# booz_power_board.net
KiCad netlist of a schematic drawn in Altium Designer
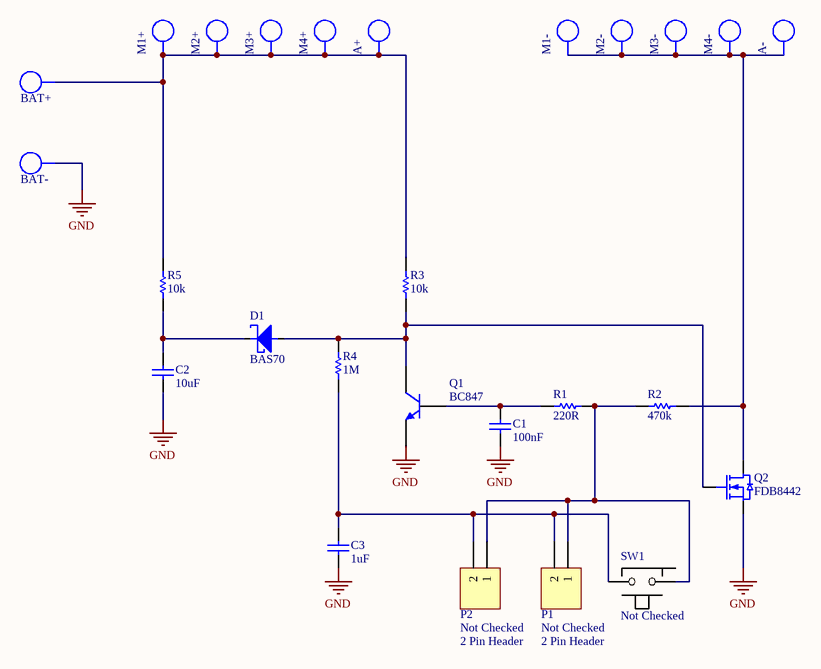
[diagram p0: booz_power_board.SchDoc]

(export (version "E")
  (design (tool "Eeschema 10.0.6"))
  (components
    (comp (ref "A+")
      (value "~")
      (footprint "BOOZ_MOTOR")
      (description "Pad for booz power board")
      (libsource (lib "GRC sch library") (part "JP_BOOZ_PAD"))
    )
    (comp (ref "A-")
      (value "~")
      (footprint "BOOZ_MOTOR")
      (description "Pad for booz power board")
      (libsource (lib "GRC sch library") (part "JP_BOOZ_PAD"))
    )
    (comp (ref "BAT+")
      (value "~")
      (footprint "BOOZ_POWER")
      (description "Pad for booz power board")
      (libsource (lib "GRC sch library") (part "JP_BOOZ_PAD"))
    )
    (comp (ref "BAT-")
      (value "~")
      (footprint "BOOZ_POWER")
      (description "Pad for booz power board")
      (libsource (lib "GRC sch library") (part "JP_BOOZ_PAD"))
    )
    (comp (ref "C1")
      (value "100nF")
      (footprint "GRC PCB library:0603")
      (description "CAP CER .10UF 50V X5R 0603")
      (fields (field (name "MANUFACTURER") "Taiyo Yuden"))
      (libsource (lib "GRC sch library") (part "CP_100nF 0603"))
    )
    (comp (ref "C2")
      (value "10uF")
      (footprint "GRC PCB library:1206")
      (description "CAP CER 10uF 25V X5R 1206")
      (fields (field (name "MANUFACTURER") "Panasonic") (field (name "Comment") "CP_10uF_25V_1206"))
      (libsource (lib "GRC sch library") (part "CP_10uF_25V_1206"))
    )
    (comp (ref "C3")
      (value "1uF")
      (footprint "GRC PCB library:0603")
      (description "CAP CER 1.0UF 50V X5S 0603")
      (fields (field (name "MANUFACTURER") "Taiyo Yuden"))
      (libsource (lib "GRC sch library") (part "CP_1uF 0603"))
    )
    (comp (ref "D1")
      (value "BAS70")
      (footprint "SOT23")
      (description "DIODE SCHOTTKY 70V 200MA SOT23")
      (fields (field (name "MANUFACTURER") "ST Micro"))
      (libsource (lib "GRC sch library") (part "DS_BAS70"))
    )
    (comp (ref "M1+")
      (value "~")
      (footprint "BOOZ_MOTOR")
      (description "Pad for booz power board")
      (libsource (lib "GRC sch library") (part "JP_BOOZ_PAD"))
    )
    (comp (ref "M1-")
      (value "~")
      (footprint "BOOZ_MOTOR")
      (description "Pad for booz power board")
      (libsource (lib "GRC sch library") (part "JP_BOOZ_PAD"))
    )
    (comp (ref "M2+")
      (value "~")
      (footprint "BOOZ_MOTOR")
      (description "Pad for booz power board")
      (libsource (lib "GRC sch library") (part "JP_BOOZ_PAD"))
    )
    (comp (ref "M2-")
      (value "~")
      (footprint "BOOZ_MOTOR")
      (description "Pad for booz power board")
      (libsource (lib "GRC sch library") (part "JP_BOOZ_PAD"))
    )
    (comp (ref "M3+")
      (value "~")
      (footprint "BOOZ_MOTOR")
      (description "Pad for booz power board")
      (libsource (lib "GRC sch library") (part "JP_BOOZ_PAD"))
    )
    (comp (ref "M3-")
      (value "~")
      (footprint "BOOZ_MOTOR")
      (description "Pad for booz power board")
      (libsource (lib "GRC sch library") (part "JP_BOOZ_PAD"))
    )
    (comp (ref "M4+")
      (value "~")
      (footprint "BOOZ_MOTOR")
      (description "Pad for booz power board")
      (libsource (lib "GRC sch library") (part "JP_BOOZ_PAD"))
    )
    (comp (ref "M4-")
      (value "~")
      (footprint "BOOZ_MOTOR")
      (description "Pad for booz power board")
      (libsource (lib "GRC sch library") (part "JP_BOOZ_PAD"))
    )
    (comp (ref "P1")
      (value "2 Pin Header")
      (footprint "CONN_2X1_SMT_RA_1.25MM")
      (description "CONN HDR VERT 2POS .100\" SNGL")
      (fields (field (name "MANUFACTURER") "Molex") (field (name "VERIFY") "Not Checked"))
      (libsource (lib "GRC sch library") (part "JP_2PIN HDR_SMT_RA_MOLEX"))
    )
    (comp (ref "P2")
      (value "2 Pin Header")
      (footprint "CONN_2X1_SMT_RA_1.25MM")
      (description "CONN HDR VERT 2POS .100\" SNGL")
      (fields (field (name "MANUFACTURER") "Molex") (field (name "VERIFY") "Not Checked"))
      (libsource (lib "GRC sch library") (part "JP_2PIN HDR_SMT_RA_MOLEX"))
    )
    (comp (ref "Q1")
      (value "BC847")
      (footprint "GRC PCB library:SOT23")
      (description "TRANS NPN GP 100MA 45V SOT23")
      (fields (field (name "MANUFACTURER") "NXP Semiconductors"))
      (libsource (lib "GRC sch library") (part "TN_BC847"))
    )
    (comp (ref "Q2")
      (value "FDB8442")
      (footprint "TO-263AB")
      (description "MOSFET N-CH 40V 80A D2PAK")
      (fields (field (name "MANUFACTURER") "Fairchild"))
      (libsource (lib "GRC sch library") (part "TF_FDB8442"))
    )
    (comp (ref "R1")
      (value "220R")
      (footprint "1206")
      (description "RES 220 OHM 1/4W 1% 1206 SMD")
      (fields (field (name "MANUFACTURER") "Vishay/Dale"))
      (libsource (lib "GRC sch library") (part "RS_220R 1206"))
    )
    (comp (ref "R2")
      (value "470k")
      (footprint "GRC PCB library:0603")
      (description "RES 470K OHM 1/10W 5% 0603 SMD")
      (fields (field (name "MANUFACTURER") "Yagep"))
      (libsource (lib "GRC sch library") (part "RS_470k 0603"))
    )
    (comp (ref "R3")
      (value "10k")
      (footprint "1206")
      (description "RES 10.0K OHM 1/4W 1% 1206 SMD")
      (fields (field (name "MANUFACTURER") "Vishay/Dale"))
      (libsource (lib "GRC sch library") (part "RS_10k 1206"))
    )
    (comp (ref "R4")
      (value "1M")
      (footprint "GRC PCB library:0603")
      (description "RES 1.00M OHM 1/10W 1% 0603 SMD")
      (fields (field (name "MANUFACTURER") "Yageo"))
      (libsource (lib "GRC sch library") (part "RS_1M 0603"))
    )
    (comp (ref "R5")
      (value "10k")
      (footprint "GRC PCB library:0603")
      (description "RES 10.0K OHM 1/10W 1% 0603 SMD")
      (fields (field (name "MANUFACTURER") "Yageo"))
      (libsource (lib "GRC sch library") (part "RS_10k 0603"))
    )
    (comp (ref "SW1")
      (value "Push Button Switch")
      (footprint "PUSHBUTTON_B3U")
      (description "SWITCH TACT RT ANG SPST SMD")
      (fields (field (name "MANUFACTURER") "Omron") (field (name "VERIFY") "Not Checked"))
      (libsource (lib "GRC sch library") (part "SW_TACT 3MM RT"))
    )
  )
  (nets
    (net (code "1") (name "GND") (class "Default")
      (node (ref "BAT-") (pin "1") (pinfunction "1_1") (pintype "power_in"))
      (node (ref "C1") (pin "1") (pinfunction "1_1") (pintype "passive"))
      (node (ref "C2") (pin "1") (pinfunction "1_1") (pintype "passive"))
      (node (ref "C3") (pin "1") (pinfunction "1_1") (pintype "passive"))
      (node (ref "Q1") (pin "2") (pinfunction "E_2") (pintype "passive"))
      (node (ref "Q2") (pin "3") (pinfunction "S_3") (pintype "passive"))
    )
    (net (code "2") (name "Net-(A+-Pad1)") (class "Default")
      (node (ref "A+") (pin "1") (pinfunction "1_1") (pintype "power_in"))
      (node (ref "BAT+") (pin "1") (pinfunction "1_1") (pintype "power_in"))
      (node (ref "M1+") (pin "1") (pinfunction "1_1") (pintype "power_in"))
      (node (ref "M2+") (pin "1") (pinfunction "1_1") (pintype "power_in"))
      (node (ref "M3+") (pin "1") (pinfunction "1_1") (pintype "power_in"))
      (node (ref "M4+") (pin "1") (pinfunction "1_1") (pintype "power_in"))
      (node (ref "R3") (pin "2") (pinfunction "2_2") (pintype "passive"))
      (node (ref "R5") (pin "2") (pinfunction "2_2") (pintype "passive"))
    )
    (net (code "3") (name "Net-(C3-Pad2)") (class "Default")
      (node (ref "C3") (pin "2") (pinfunction "2_2") (pintype "passive"))
      (node (ref "P1") (pin "2") (pinfunction "2_2") (pintype "passive"))
      (node (ref "P2") (pin "2") (pinfunction "2_2") (pintype "passive"))
      (node (ref "R4") (pin "1") (pinfunction "1_1") (pintype "passive"))
      (node (ref "SW1") (pin "2") (pinfunction "2_2") (pintype "passive"))
    )
    (net (code "4") (name "Net-(D1-A)") (class "Default")
      (node (ref "D1") (pin "1") (pinfunction "A_1") (pintype "passive"))
      (node (ref "Q1") (pin "3") (pinfunction "C_3") (pintype "passive"))
      (node (ref "Q2") (pin "1") (pinfunction "G_1") (pintype "passive"))
      (node (ref "R3") (pin "1") (pinfunction "1_1") (pintype "passive"))
      (node (ref "R4") (pin "2") (pinfunction "2_2") (pintype "passive"))
    )
    (net (code "5") (name "Net-(D1-K)") (class "Default")
      (node (ref "C2") (pin "2") (pinfunction "2_2") (pintype "passive"))
      (node (ref "D1") (pin "3") (pinfunction "K_3") (pintype "passive"))
      (node (ref "R5") (pin "1") (pinfunction "1_1") (pintype "passive"))
    )
    (net (code "6") (name "Net-(P1-Pad1)") (class "Default")
      (node (ref "P1") (pin "1") (pinfunction "1_1") (pintype "passive"))
      (node (ref "P2") (pin "1") (pinfunction "1_1") (pintype "passive"))
      (node (ref "R1") (pin "2") (pinfunction "2_2") (pintype "passive"))
      (node (ref "R2") (pin "1") (pinfunction "1_1") (pintype "passive"))
      (node (ref "SW1") (pin "1") (pinfunction "1_1") (pintype "passive"))
    )
    (net (code "7") (name "Net-(Q1-B)") (class "Default")
      (node (ref "C1") (pin "2") (pinfunction "2_2") (pintype "passive"))
      (node (ref "Q1") (pin "1") (pinfunction "B_1") (pintype "passive"))
      (node (ref "R1") (pin "1") (pinfunction "1_1") (pintype "passive"))
    )
    (net (code "8") (name "Net-(Q2-D)") (class "Default")
      (node (ref "A-") (pin "1") (pinfunction "1_1") (pintype "power_in"))
      (node (ref "M1-") (pin "1") (pinfunction "1_1") (pintype "power_in"))
      (node (ref "M2-") (pin "1") (pinfunction "1_1") (pintype "power_in"))
      (node (ref "M3-") (pin "1") (pinfunction "1_1") (pintype "power_in"))
      (node (ref "M4-") (pin "1") (pinfunction "1_1") (pintype "power_in"))
      (node (ref "Q2") (pin "4") (pinfunction "D_4") (pintype "passive"))
      (node (ref "R2") (pin "2") (pinfunction "2_2") (pintype "passive"))
    )
    (net (code "9") (name "unconnected-(SW1-GND-Pad3)") (class "Default")
      (node (ref "SW1") (pin "3") (pinfunction "GND_3") (pintype "passive"))
    )
  )
)
